# pressure_sensors.net
KiCad netlist of a schematic drawn in EAGLE
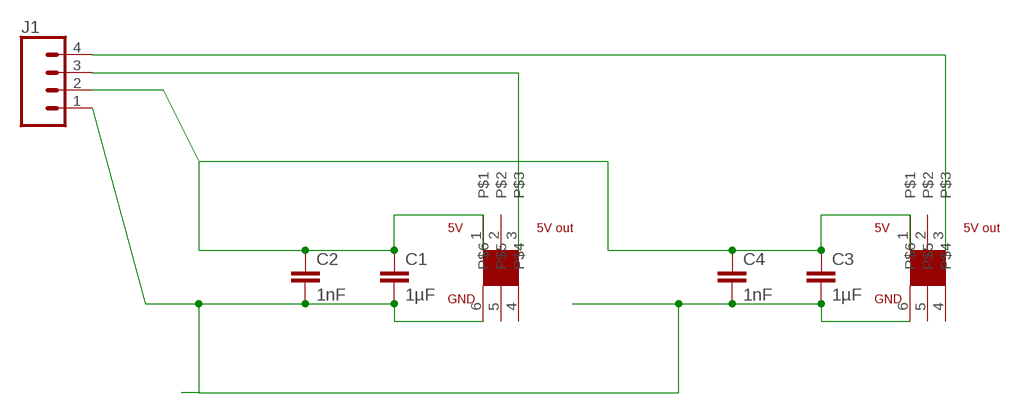
[diagram p0: schematic, sheet 1]

(export (version "E")
  (design (tool "Eeschema 10.0.6"))
  (components
    (comp (ref "C1")
      (value "1µF")
      (footprint "eagle-import:C050-030X075")
      (libsource (lib "eagle-import") (part "C-EU050-030X075"))
    )
    (comp (ref "C2")
      (value "1nF")
      (footprint "eagle-import:C050-030X075")
      (libsource (lib "eagle-import") (part "C-EU050-030X075"))
    )
    (comp (ref "C3")
      (value "1µF")
      (footprint "eagle-import:C050-030X075")
      (libsource (lib "eagle-import") (part "C-EU050-030X075"))
    )
    (comp (ref "C4")
      (value "1nF")
      (footprint "eagle-import:C050-030X075")
      (libsource (lib "eagle-import") (part "C-EU050-030X075"))
    )
    (comp (ref "J1")
      (value "CONN_04")
      (footprint "eagle-import:1X04")
      (libsource (lib "eagle-import") (part "CONN_04"))
    )
    (comp (ref "U$1")
      (value "ADP5101")
      (footprint "eagle-import:DIP750W53P254L720H850Q6B")
      (libsource (lib "eagle-import") (part "ADP5101"))
    )
    (comp (ref "U$2")
      (value "ADP5101")
      (footprint "eagle-import:DIP750W53P254L720H850Q6B")
      (libsource (lib "eagle-import") (part "ADP5101"))
    )
  )
  (nets
    (net (code "1") (name "Net-(U$1-P$1)") (class "Default")
      (node (ref "C1") (pin "1") (pinfunction "1_1") (pintype "passive"))
      (node (ref "C2") (pin "1") (pinfunction "1_1") (pintype "passive"))
      (node (ref "C3") (pin "1") (pinfunction "1_1") (pintype "passive"))
      (node (ref "C4") (pin "1") (pinfunction "1_1") (pintype "passive"))
      (node (ref "J1") (pin "2") (pinfunction "2_2") (pintype "passive"))
      (node (ref "U$1") (pin "1") (pinfunction "P$1_1") (pintype "power_in"))
      (node (ref "U$2") (pin "1") (pinfunction "P$1_1") (pintype "power_in"))
    )
    (net (code "2") (name "Net-(U$1-P$3)") (class "Default")
      (node (ref "J1") (pin "3") (pinfunction "3_3") (pintype "passive"))
      (node (ref "U$1") (pin "3") (pinfunction "P$3_3") (pintype "output"))
    )
    (net (code "3") (name "Net-(U$1-P$6)") (class "Default")
      (node (ref "C1") (pin "2") (pinfunction "2_2") (pintype "passive"))
      (node (ref "C2") (pin "2") (pinfunction "2_2") (pintype "passive"))
      (node (ref "C3") (pin "2") (pinfunction "2_2") (pintype "passive"))
      (node (ref "C4") (pin "2") (pinfunction "2_2") (pintype "passive"))
      (node (ref "J1") (pin "1") (pinfunction "1_1") (pintype "passive"))
      (node (ref "U$1") (pin "6") (pinfunction "P$6_6") (pintype "power_in"))
      (node (ref "U$2") (pin "6") (pinfunction "P$6_6") (pintype "power_in"))
    )
    (net (code "4") (name "Net-(U$2-P$3)") (class "Default")
      (node (ref "J1") (pin "4") (pinfunction "4_4") (pintype "passive"))
      (node (ref "U$2") (pin "3") (pinfunction "P$3_3") (pintype "output"))
    )
    (net (code "5") (name "unconnected-(U$1-P$2-Pad2)") (class "Default")
      (node (ref "U$1") (pin "2") (pinfunction "P$2_2") (pintype "no_connect"))
    )
    (net (code "6") (name "unconnected-(U$1-P$4-Pad4)") (class "Default")
      (node (ref "U$1") (pin "4") (pinfunction "P$4_4") (pintype "no_connect"))
    )
    (net (code "7") (name "unconnected-(U$1-P$5-Pad5)") (class "Default")
      (node (ref "U$1") (pin "5") (pinfunction "P$5_5") (pintype "no_connect"))
    )
    (net (code "8") (name "unconnected-(U$2-P$2-Pad2)") (class "Default")
      (node (ref "U$2") (pin "2") (pinfunction "P$2_2") (pintype "no_connect"))
    )
    (net (code "9") (name "unconnected-(U$2-P$4-Pad4)") (class "Default")
      (node (ref "U$2") (pin "4") (pinfunction "P$4_4") (pintype "no_connect"))
    )
    (net (code "10") (name "unconnected-(U$2-P$5-Pad5)") (class "Default")
      (node (ref "U$2") (pin "5") (pinfunction "P$5_5") (pintype "no_connect"))
    )
  )
)
